# KDT3ADDAMP-093.net
KiCad netlist of a schematic drawn in EasyEDA Pro
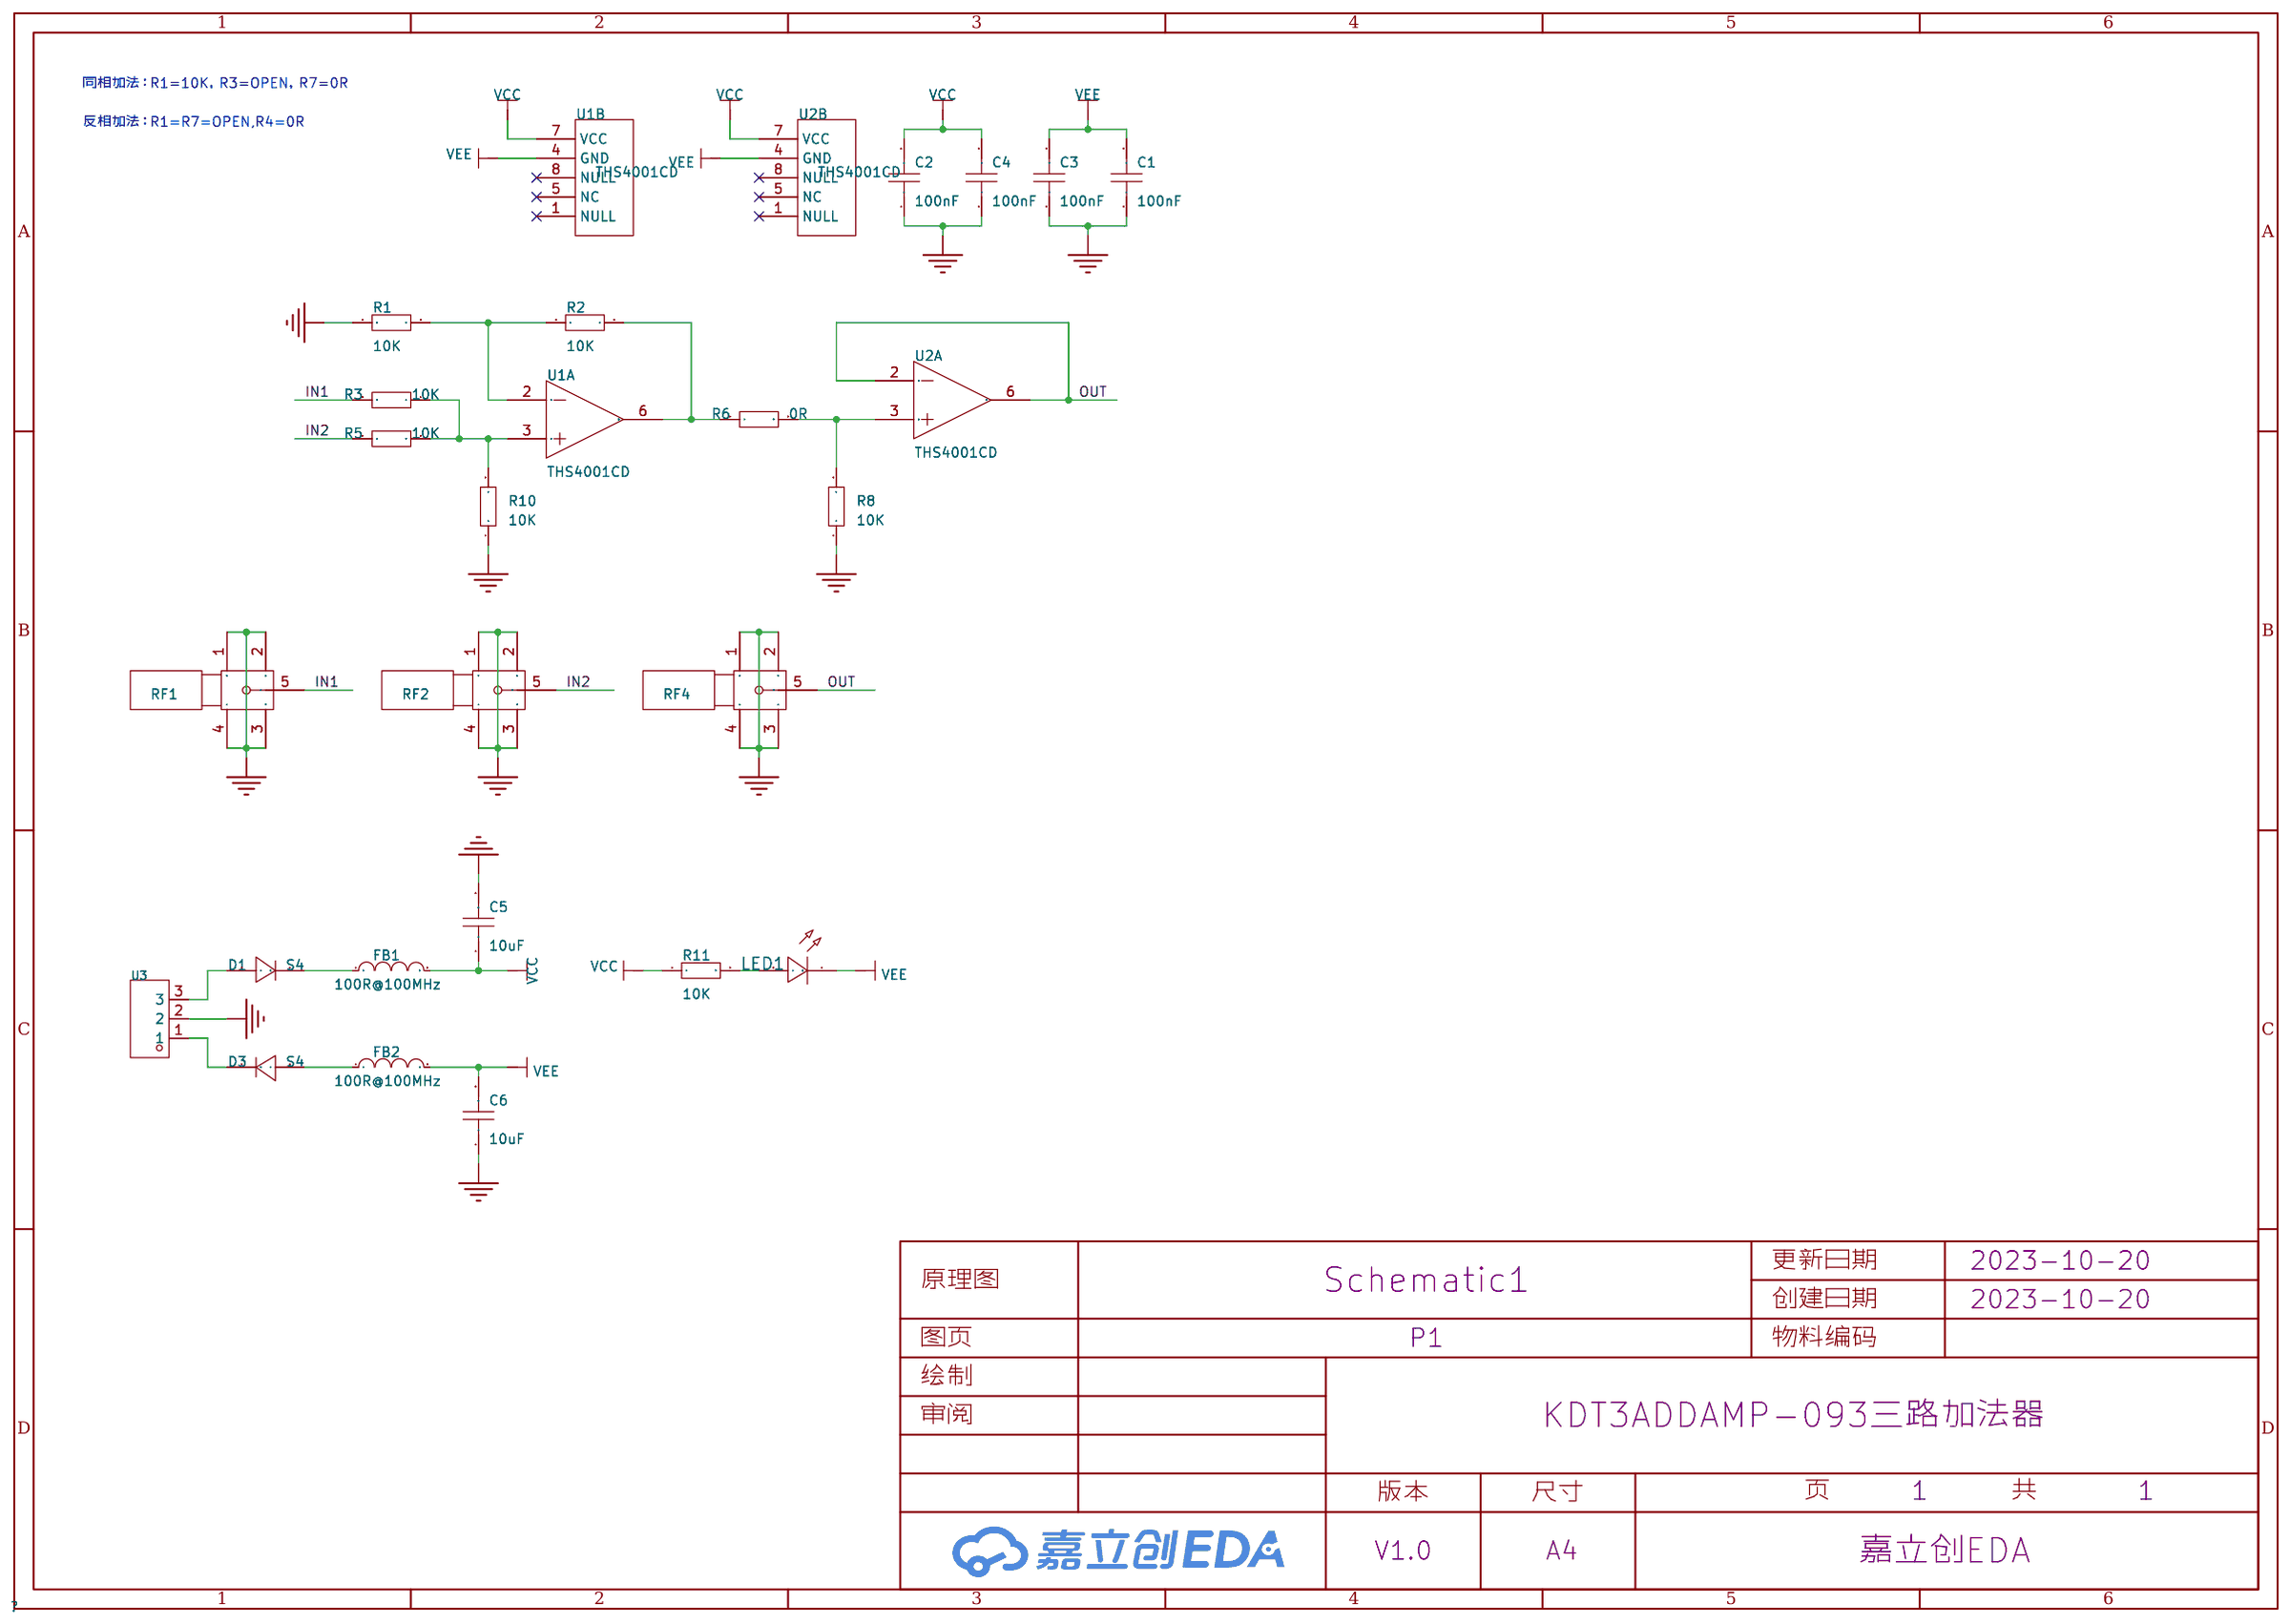
[diagram p0: schematic sheet]

(export (version "E")
  (design (tool "Eeschema 10.0.6"))
  (components
    (comp (ref "C1")
      (value "100nF")
      (footprint "easyedapro:C1206")
      (libsource (lib "easyedapro") (part "CapAcitance"))
    )
    (comp (ref "C2")
      (value "100nF")
      (footprint "easyedapro:C1206")
      (libsource (lib "easyedapro") (part "CapAcitance"))
    )
    (comp (ref "C3")
      (value "100nF")
      (footprint "easyedapro:C1206")
      (libsource (lib "easyedapro") (part "CapAcitance"))
    )
    (comp (ref "C4")
      (value "100nF")
      (footprint "easyedapro:C1206")
      (libsource (lib "easyedapro") (part "CapAcitance"))
    )
    (comp (ref "C5")
      (value "10uF")
      (footprint "easyedapro:C1206")
      (libsource (lib "easyedapro") (part "CapAcitance"))
    )
    (comp (ref "C6")
      (value "10uF")
      (footprint "easyedapro:C1206")
      (libsource (lib "easyedapro") (part "CapAcitance"))
    )
    (comp (ref "D1")
      (value "S4")
      (footprint "easyedapro:SOD-323_L1.8-W1.3-LS2.5-RD")
      (description "直流反向耐压(Vr):40V;平均整流电流(Io):350mA;正向压降(Vf):600mV@200mA;")
      (fields (field (name "Manufacturer") "CJ(江苏长电/长晶)"))
      (libsource (lib "easyedapro") (part "SD103AWS_C8607"))
    )
    (comp (ref "D3")
      (value "S4")
      (footprint "easyedapro:SOD-323_L1.8-W1.3-LS2.5-RD")
      (description "直流反向耐压(Vr):40V;平均整流电流(Io):350mA;正向压降(Vf):600mV@200mA;")
      (fields (field (name "Manufacturer") "CJ(江苏长电/长晶)"))
      (libsource (lib "easyedapro") (part "SD103AWS_C8607"))
    )
    (comp (ref "FB1")
      (value "100R@100MHz")
      (footprint "easyedapro:L0603")
      (description "标称阻抗@测试频率:100Ω@100MHz;误差:±25%;直流电阻(RDC):30mΩ;额定电流:3A;电路数:1;")
      (fields (field (name "Manufacturer") "Sunlord(顺络)"))
      (libsource (lib "easyedapro") (part "UPZ1608E101-3R0TF"))
    )
    (comp (ref "FB2")
      (value "100R@100MHz")
      (footprint "easyedapro:L0603")
      (description "标称阻抗@测试频率:100Ω@100MHz;误差:±25%;直流电阻(RDC):30mΩ;额定电流:3A;电路数:1;")
      (fields (field (name "Manufacturer") "Sunlord(顺络)"))
      (libsource (lib "easyedapro") (part "UPZ1608E101-3R0TF"))
    )
    (comp (ref "LED1")
      (value "~")
      (footprint "easyedapro:LED_0603")
      (libsource (lib "easyedapro") (part "LED_R"))
    )
    (comp (ref "R1") (value "10K") (footprint "easyedapro:R0603") (libsource (lib "easyedapro") (part "电阻")))
    (comp (ref "R2") (value "10K") (footprint "easyedapro:R0603") (libsource (lib "easyedapro") (part "电阻")))
    (comp (ref "R3") (value "10K") (footprint "easyedapro:R0603") (libsource (lib "easyedapro") (part "电阻")))
    (comp (ref "R5") (value "10K") (footprint "easyedapro:R0603") (libsource (lib "easyedapro") (part "电阻")))
    (comp (ref "R6") (value "0R") (footprint "easyedapro:R0603") (libsource (lib "easyedapro") (part "电阻")))
    (comp (ref "R8") (value "10K") (footprint "easyedapro:R0603") (libsource (lib "easyedapro") (part "电阻")))
    (comp (ref "R10") (value "10K") (footprint "easyedapro:R0603") (libsource (lib "easyedapro") (part "电阻")))
    (comp (ref "R11") (value "10K") (footprint "easyedapro:R0603") (libsource (lib "easyedapro") (part "电阻")))
    (comp (ref "RF1")
      (value "BWSMA-KE-P001")
      (footprint "easyedapro:SMA-SMD_BWSMA-KE-P001")
      (description "连接器类型:板端;射频系列:SMA;接口类型:内孔;端口数量:1;阻抗:50Ω;频率-最大值:12.4GHz;样式:偏脚;接口直径:5.2mm;接口长度/高度:-;工作温度范围:-;")
      (fields (field (name "Manufacturer") "BAT WIRELESS(蝙蝠无线)"))
      (libsource (lib "easyedapro") (part "BWSMA-KE-P001"))
    )
    (comp (ref "RF2")
      (value "BWSMA-KE-P001")
      (footprint "easyedapro:SMA-SMD_BWSMA-KE-P001")
      (description "连接器类型:板端;射频系列:SMA;接口类型:内孔;端口数量:1;阻抗:50Ω;频率-最大值:12.4GHz;样式:偏脚;接口直径:5.2mm;接口长度/高度:-;工作温度范围:-;")
      (fields (field (name "Manufacturer") "BAT WIRELESS(蝙蝠无线)"))
      (libsource (lib "easyedapro") (part "BWSMA-KE-P001"))
    )
    (comp (ref "RF4")
      (value "BWSMA-KE-P001")
      (footprint "easyedapro:SMA-SMD_BWSMA-KE-P001")
      (description "连接器类型:板端;射频系列:SMA;接口类型:内孔;端口数量:1;阻抗:50Ω;频率-最大值:12.4GHz;样式:偏脚;接口直径:5.2mm;接口长度/高度:-;工作温度范围:-;")
      (fields (field (name "Manufacturer") "BAT WIRELESS(蝙蝠无线)"))
      (libsource (lib "easyedapro") (part "BWSMA-KE-P001"))
    )
    (comp (ref "U1")
      (value "THS4001CD")
      (footprint "easyedapro:SOIC-8_L5.0-W4.0-P1.27-LS6.0-BL")
      (description "放大器组数:-;")
      (fields (field (name "Manufacturer") "TI(德州仪器)"))
      (libsource (lib "easyedapro") (part "THS4001CD"))
    )
    (comp (ref "U2")
      (value "THS4001CD")
      (footprint "easyedapro:SOIC-8_L5.0-W4.0-P1.27-LS6.0-BL")
      (description "放大器组数:-;")
      (fields (field (name "Manufacturer") "TI(德州仪器)"))
      (libsource (lib "easyedapro") (part "THS4001CD"))
    )
    (comp (ref "U3")
      (value "HCZZ0126-3")
      (footprint "easyedapro:CONN-TH_3P-P2.50_3PIN")
      (fields (field (name "Manufacturer") "HC(虹成电子)"))
      (libsource (lib "easyedapro") (part "HCZZ0126-3"))
    )
  )
  (nets
    (net (code "1") (name "/IN1") (class "Default")
      (node (ref "R3") (pin "2") (pinfunction "2_2") (pintype "input"))
      (node (ref "RF1") (pin "5") (pinfunction "5_5") (pintype "input"))
    )
    (net (code "2") (name "/IN2") (class "Default")
      (node (ref "R5") (pin "1") (pinfunction "1_1") (pintype "input"))
      (node (ref "RF2") (pin "5") (pinfunction "5_5") (pintype "input"))
    )
    (net (code "3") (name "/OUT") (class "Default")
      (node (ref "RF4") (pin "5") (pinfunction "5_5") (pintype "input"))
      (node (ref "U2") (pin "2") (pinfunction "IN-_2") (pintype "input"))
      (node (ref "U2") (pin "6") (pinfunction "OUT_6") (pintype "input"))
    )
    (net (code "4") (name "GND") (class "Default")
      (node (ref "C1") (pin "1") (pinfunction "1_1") (pintype "input"))
      (node (ref "C2") (pin "1") (pinfunction "1_1") (pintype "input"))
      (node (ref "C3") (pin "1") (pinfunction "1_1") (pintype "input"))
      (node (ref "C4") (pin "1") (pinfunction "1_1") (pintype "input"))
      (node (ref "C5") (pin "2") (pinfunction "2_2") (pintype "input"))
      (node (ref "C6") (pin "1") (pinfunction "1_1") (pintype "input"))
      (node (ref "R1") (pin "1") (pinfunction "1_1") (pintype "input"))
      (node (ref "R10") (pin "1") (pinfunction "1_1") (pintype "input"))
      (node (ref "R8") (pin "1") (pinfunction "1_1") (pintype "input"))
      (node (ref "RF1") (pin "1") (pinfunction "1_1") (pintype "input"))
      (node (ref "RF1") (pin "2") (pinfunction "2_2") (pintype "input"))
      (node (ref "RF1") (pin "3") (pinfunction "3_3") (pintype "input"))
      (node (ref "RF1") (pin "4") (pinfunction "4_4") (pintype "input"))
      (node (ref "RF2") (pin "1") (pinfunction "1_1") (pintype "input"))
      (node (ref "RF2") (pin "2") (pinfunction "2_2") (pintype "input"))
      (node (ref "RF2") (pin "3") (pinfunction "3_3") (pintype "input"))
      (node (ref "RF2") (pin "4") (pinfunction "4_4") (pintype "input"))
      (node (ref "RF4") (pin "1") (pinfunction "1_1") (pintype "input"))
      (node (ref "RF4") (pin "2") (pinfunction "2_2") (pintype "input"))
      (node (ref "RF4") (pin "3") (pinfunction "3_3") (pintype "input"))
      (node (ref "RF4") (pin "4") (pinfunction "4_4") (pintype "input"))
      (node (ref "U3") (pin "2") (pinfunction "2_2") (pintype "input"))
    )
    (net (code "5") (name "Net-(D1-A)") (class "Default")
      (node (ref "D1") (pin "2") (pinfunction "A_2") (pintype "input"))
      (node (ref "U3") (pin "3") (pinfunction "3_3") (pintype "input"))
    )
    (net (code "6") (name "Net-(D1-C)") (class "Default")
      (node (ref "D1") (pin "1") (pinfunction "C_1") (pintype "input"))
      (node (ref "FB1") (pin "1") (pinfunction "1_1") (pintype "input"))
    )
    (net (code "7") (name "Net-(D3-A)") (class "Default")
      (node (ref "D3") (pin "2") (pinfunction "A_2") (pintype "input"))
      (node (ref "FB2") (pin "1") (pinfunction "1_1") (pintype "input"))
    )
    (net (code "8") (name "Net-(D3-C)") (class "Default")
      (node (ref "D3") (pin "1") (pinfunction "C_1") (pintype "input"))
      (node (ref "U3") (pin "1") (pinfunction "1_1") (pintype "input"))
    )
    (net (code "9") (name "Net-(LED1-A)") (class "Default")
      (node (ref "LED1") (pin "2") (pinfunction "A_2") (pintype "input"))
      (node (ref "R11") (pin "2") (pinfunction "2_2") (pintype "input"))
    )
    (net (code "10") (name "Net-(U1A-IN+)") (class "Default")
      (node (ref "R10") (pin "2") (pinfunction "2_2") (pintype "input"))
      (node (ref "R3") (pin "1") (pinfunction "1_1") (pintype "input"))
      (node (ref "R5") (pin "2") (pinfunction "2_2") (pintype "input"))
      (node (ref "U1") (pin "3") (pinfunction "IN+_3") (pintype "input"))
    )
    (net (code "11") (name "Net-(U1A-IN-)") (class "Default")
      (node (ref "R1") (pin "2") (pinfunction "2_2") (pintype "input"))
      (node (ref "R2") (pin "1") (pinfunction "1_1") (pintype "input"))
      (node (ref "U1") (pin "2") (pinfunction "IN-_2") (pintype "input"))
    )
    (net (code "12") (name "Net-(U1A-OUT)") (class "Default")
      (node (ref "R2") (pin "2") (pinfunction "2_2") (pintype "input"))
      (node (ref "R6") (pin "1") (pinfunction "1_1") (pintype "input"))
      (node (ref "U1") (pin "6") (pinfunction "OUT_6") (pintype "input"))
    )
    (net (code "13") (name "Net-(U2A-IN+)") (class "Default")
      (node (ref "R6") (pin "2") (pinfunction "2_2") (pintype "input"))
      (node (ref "R8") (pin "2") (pinfunction "2_2") (pintype "input"))
      (node (ref "U2") (pin "3") (pinfunction "IN+_3") (pintype "input"))
    )
    (net (code "14") (name "VCC") (class "Default")
      (node (ref "C2") (pin "2") (pinfunction "2_2") (pintype "input"))
      (node (ref "C4") (pin "2") (pinfunction "2_2") (pintype "input"))
      (node (ref "C5") (pin "1") (pinfunction "1_1") (pintype "input"))
      (node (ref "FB1") (pin "2") (pinfunction "2_2") (pintype "input"))
      (node (ref "R11") (pin "1") (pinfunction "1_1") (pintype "input"))
      (node (ref "U1") (pin "7") (pinfunction "VCC_7") (pintype "input"))
      (node (ref "U2") (pin "7") (pinfunction "VCC_7") (pintype "input"))
    )
    (net (code "15") (name "VEE") (class "Default")
      (node (ref "C1") (pin "2") (pinfunction "2_2") (pintype "input"))
      (node (ref "C3") (pin "2") (pinfunction "2_2") (pintype "input"))
      (node (ref "C6") (pin "2") (pinfunction "2_2") (pintype "input"))
      (node (ref "FB2") (pin "2") (pinfunction "2_2") (pintype "input"))
      (node (ref "LED1") (pin "1") (pinfunction "C_1") (pintype "input"))
      (node (ref "U1") (pin "4") (pinfunction "GND_4") (pintype "input"))
      (node (ref "U2") (pin "4") (pinfunction "GND_4") (pintype "input"))
    )
    (net (code "16") (name "unconnected-(U1B-NC-Pad5)") (class "Default")
      (node (ref "U1") (pin "5") (pinfunction "NC_5") (pintype "input+no_connect"))
    )
    (net (code "17") (name "unconnected-(U1B-NULL-Pad1)") (class "Default")
      (node (ref "U1") (pin "1") (pinfunction "NULL_1") (pintype "input+no_connect"))
    )
    (net (code "18") (name "unconnected-(U1B-NULL-Pad8)") (class "Default")
      (node (ref "U1") (pin "8") (pinfunction "NULL_8") (pintype "input+no_connect"))
    )
    (net (code "19") (name "unconnected-(U2B-NC-Pad5)") (class "Default")
      (node (ref "U2") (pin "5") (pinfunction "NC_5") (pintype "input+no_connect"))
    )
    (net (code "20") (name "unconnected-(U2B-NULL-Pad1)") (class "Default")
      (node (ref "U2") (pin "1") (pinfunction "NULL_1") (pintype "input+no_connect"))
    )
    (net (code "21") (name "unconnected-(U2B-NULL-Pad8)") (class "Default")
      (node (ref "U2") (pin "8") (pinfunction "NULL_8") (pintype "input+no_connect"))
    )
  )
)
